# ProDuino.net
KiCad netlist of a schematic drawn in EAGLE
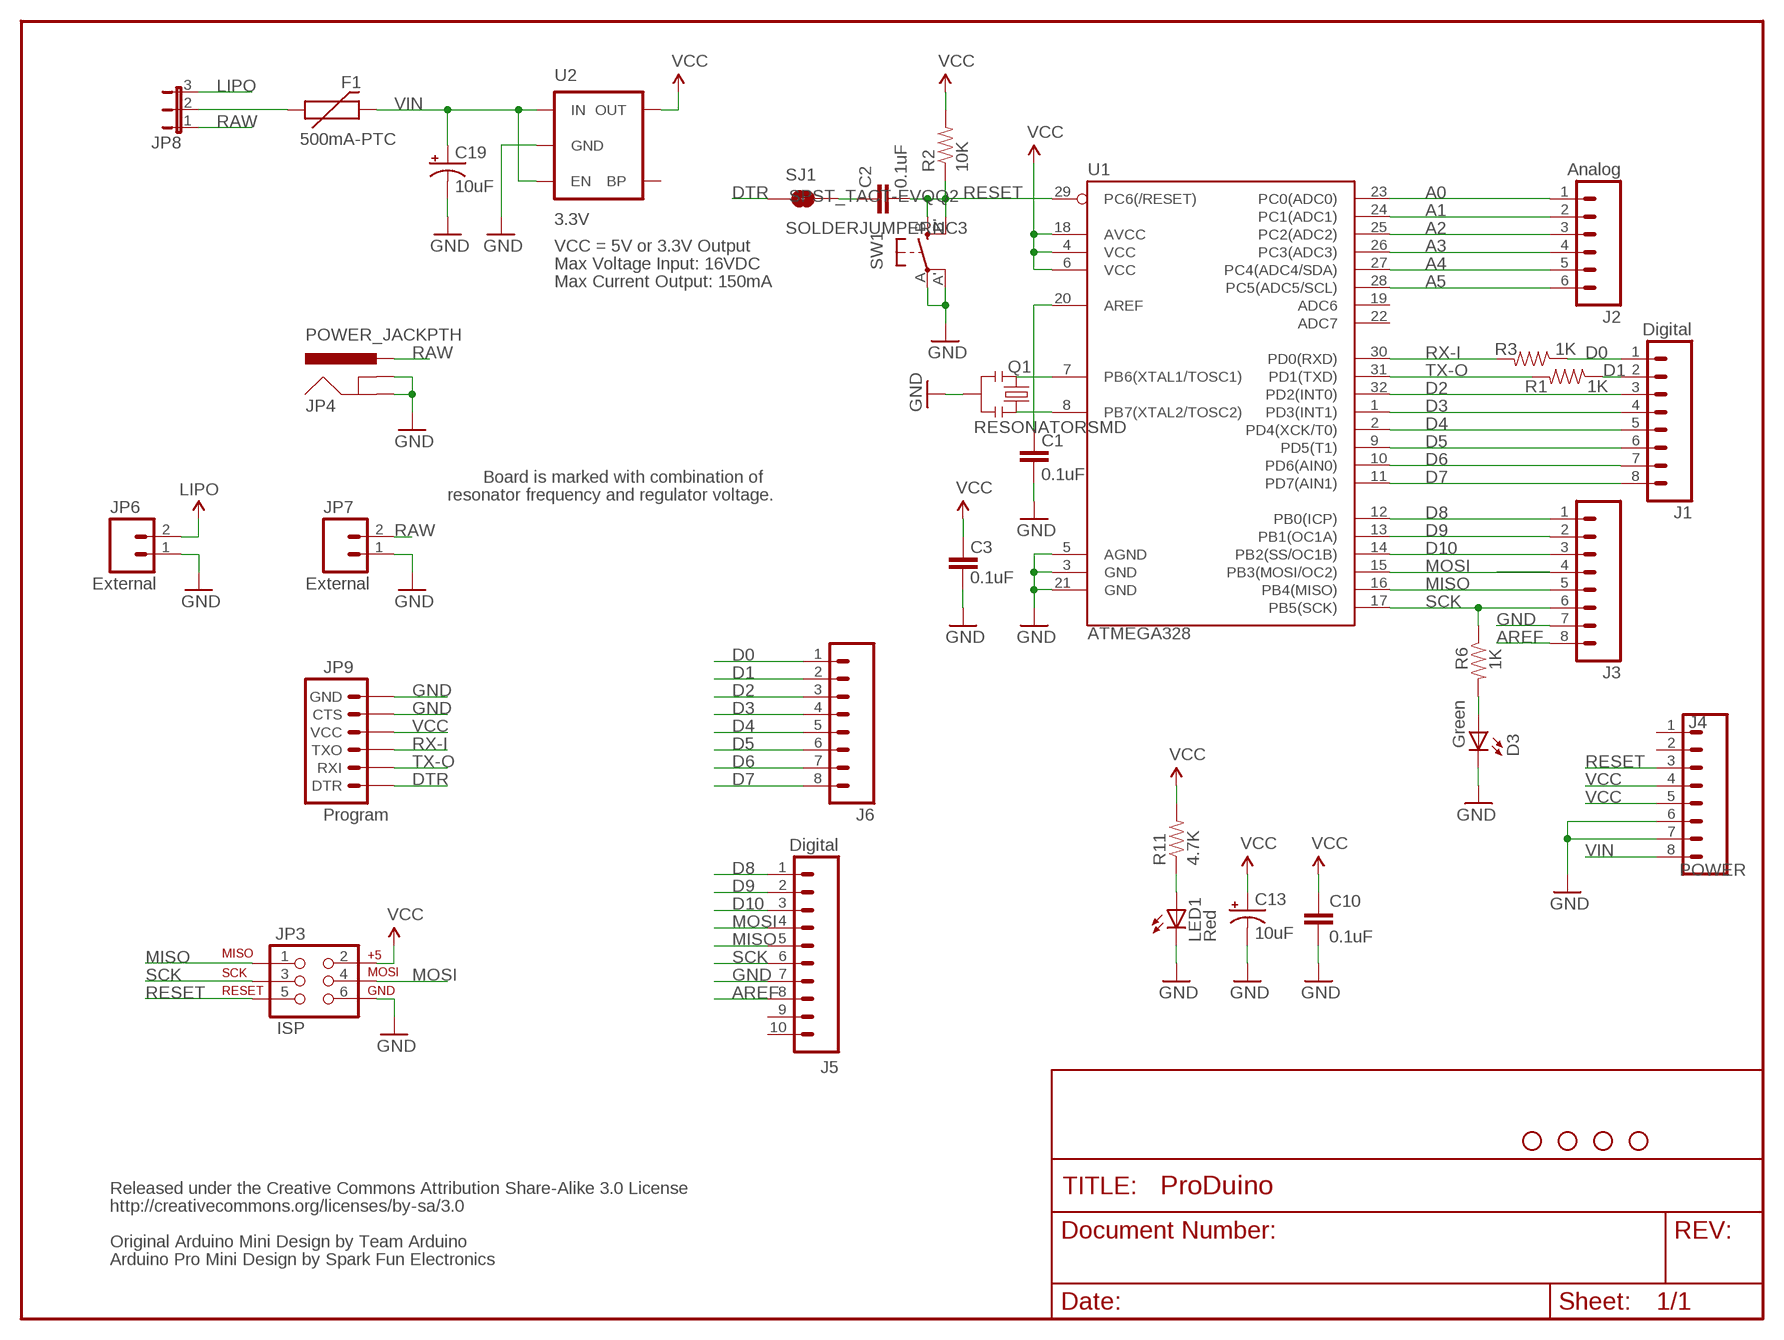
[diagram p0: schematic, sheet 1]

(export (version "E")
  (design (tool "Eeschema 10.0.6"))
  (components
    (comp (ref "C1")
      (value "0.1uF")
      (footprint "eagle-import:0603-CAP")
      (libsource (lib "eagle-import") (part "CAP0603-CAP"))
    )
    (comp (ref "C2")
      (value "0.1uF")
      (footprint "eagle-import:0603-CAP")
      (libsource (lib "eagle-import") (part "CAP0603-CAP"))
    )
    (comp (ref "C3")
      (value "0.1uF")
      (footprint "eagle-import:0603-CAP")
      (libsource (lib "eagle-import") (part "CAP0603-CAP"))
    )
    (comp (ref "C10")
      (value "0.1uF")
      (footprint "eagle-import:0603-CAP")
      (libsource (lib "eagle-import") (part "CAP0603-CAP"))
    )
    (comp (ref "C13")
      (value "10uF")
      (footprint "eagle-import:EIA3216")
      (libsource (lib "eagle-import") (part "CAP_POL1206"))
    )
    (comp (ref "C19")
      (value "10uF")
      (footprint "eagle-import:EIA3216")
      (libsource (lib "eagle-import") (part "CAP_POL1206"))
    )
    (comp (ref "D3")
      (value "Green")
      (footprint "eagle-import:LED-0603")
      (libsource (lib "eagle-import") (part "LED0603"))
    )
    (comp (ref "F1")
      (value "500mA-PTC")
      (footprint "eagle-import:PTC-1206")
      (libsource (lib "eagle-import") (part "PTCSMD"))
    )
    (comp (ref "J1")
      (value "Digital")
      (footprint "eagle-import:1X08")
      (libsource (lib "eagle-import") (part "M081X08"))
    )
    (comp (ref "J2")
      (value "Analog")
      (footprint "eagle-import:1X06")
      (libsource (lib "eagle-import") (part "M06SIP"))
    )
    (comp (ref "J3")
      (value "M081X08")
      (footprint "eagle-import:1X08")
      (libsource (lib "eagle-import") (part "M081X08"))
    )
    (comp (ref "J4")
      (value "POWER")
      (footprint "eagle-import:1X08")
      (libsource (lib "eagle-import") (part "SparkFun-Connectors_M081X08"))
    )
    (comp (ref "J5")
      (value "Digital")
      (footprint "eagle-import:1X10")
      (libsource (lib "eagle-import") (part "M10{dblquote}"))
    )
    (comp (ref "J6")
      (value "M081X08")
      (footprint "eagle-import:1X08")
      (libsource (lib "eagle-import") (part "M081X08"))
    )
    (comp (ref "JP3")
      (value "ISP")
      (footprint "eagle-import:2X3")
      (libsource (lib "eagle-import") (part "AVR_SPI_PRG_6PTH"))
    )
    (comp (ref "JP4")
      (value "POWER_JACKPTH")
      (footprint "eagle-import:POWER_JACK_PTH")
      (libsource (lib "eagle-import") (part "POWER_JACKPTH"))
    )
    (comp (ref "JP6")
      (value "External")
      (footprint "eagle-import:1X02")
      (libsource (lib "eagle-import") (part "M02PTH"))
    )
    (comp (ref "JP7")
      (value "External")
      (footprint "eagle-import:1X02")
      (libsource (lib "eagle-import") (part "M02PTH"))
    )
    (comp (ref "JP8")
      (value "JP2E")
      (footprint "eagle-import:JP2")
      (libsource (lib "eagle-import") (part "JP2E"))
    )
    (comp (ref "JP9")
      (value "Program")
      (footprint "eagle-import:1X06")
      (libsource (lib "eagle-import") (part "ARDUINO_SERIAL_PROGRAMPTH"))
    )
    (comp (ref "LED1")
      (value "Red")
      (footprint "eagle-import:LED-0603")
      (libsource (lib "eagle-import") (part "LED0603"))
    )
    (comp (ref "Q1")
      (value "RESONATORSMD")
      (footprint "eagle-import:RESONATOR-SMD")
      (libsource (lib "eagle-import") (part "RESONATORSMD"))
    )
    (comp (ref "R1")
      (value "1K")
      (footprint "eagle-import:0603-RES")
      (libsource (lib "eagle-import") (part "RESISTOR0603-RES"))
    )
    (comp (ref "R2")
      (value "10K")
      (footprint "eagle-import:0603-RES")
      (libsource (lib "eagle-import") (part "RESISTOR0603-RES"))
    )
    (comp (ref "R3")
      (value "1K")
      (footprint "eagle-import:0603-RES")
      (libsource (lib "eagle-import") (part "RESISTOR0603-RES"))
    )
    (comp (ref "R6")
      (value "1K")
      (footprint "eagle-import:0603-RES")
      (libsource (lib "eagle-import") (part "RESISTOR0603-RES"))
    )
    (comp (ref "R11")
      (value "4.7K")
      (footprint "eagle-import:0603-RES")
      (libsource (lib "eagle-import") (part "RESISTOR0603-RES"))
    )
    (comp (ref "SJ1")
      (value "SOLDERJUMPERNC3")
      (footprint "eagle-import:SJ_2S-NOTRACE")
      (libsource (lib "eagle-import") (part "SOLDERJUMPERNC2"))
    )
    (comp (ref "SW1")
      (value "SPST_TACT-EVQQ2")
      (footprint "eagle-import:EVQ-Q2")
      (libsource (lib "eagle-import") (part "SPST_TACT-EVQQ2"))
    )
    (comp (ref "U$1")
      (value "STAND-OFF")
      (footprint "eagle-import:STAND-OFF")
      (libsource (lib "eagle-import") (part "STAND-OFF"))
    )
    (comp (ref "U$3")
      (value "STAND-OFF")
      (footprint "eagle-import:STAND-OFF")
      (libsource (lib "eagle-import") (part "STAND-OFF"))
    )
    (comp (ref "U$9")
      (value "STAND-OFF")
      (footprint "eagle-import:STAND-OFF")
      (libsource (lib "eagle-import") (part "STAND-OFF"))
    )
    (comp (ref "U$10")
      (value "STAND-OFF")
      (footprint "eagle-import:STAND-OFF")
      (libsource (lib "eagle-import") (part "STAND-OFF"))
    )
    (comp (ref "U1")
      (value "ATMEGA328")
      (footprint "eagle-import:TQFP32-08")
      (libsource (lib "eagle-import") (part "ATMEGA168"))
    )
    (comp (ref "U2")
      (value "3.3V")
      (footprint "eagle-import:SOT23-5")
      (libsource (lib "eagle-import") (part "V_REG_LDOSMD"))
    )
  )
  (nets
    (net (code "1") (name "/A0") (class "Default")
      (node (ref "J2") (pin "1") (pinfunction "1_1") (pintype "passive"))
      (node (ref "U1") (pin "23") (pinfunction "PC0(ADC0)_23") (pintype "bidirectional"))
    )
    (net (code "2") (name "/A1") (class "Default")
      (node (ref "J2") (pin "2") (pinfunction "2_2") (pintype "passive"))
      (node (ref "U1") (pin "24") (pinfunction "PC1(ADC1)_24") (pintype "bidirectional"))
    )
    (net (code "3") (name "/A2") (class "Default")
      (node (ref "J2") (pin "3") (pinfunction "3_3") (pintype "passive"))
      (node (ref "U1") (pin "25") (pinfunction "PC2(ADC2)_25") (pintype "bidirectional"))
    )
    (net (code "4") (name "/A3") (class "Default")
      (node (ref "J2") (pin "4") (pinfunction "4_4") (pintype "passive"))
      (node (ref "U1") (pin "26") (pinfunction "PC3(ADC3)_26") (pintype "bidirectional"))
    )
    (net (code "5") (name "/A4") (class "Default")
      (node (ref "J2") (pin "5") (pinfunction "5_5") (pintype "passive"))
      (node (ref "U1") (pin "27") (pinfunction "PC4(ADC4/SDA)_27") (pintype "bidirectional"))
    )
    (net (code "6") (name "/A5") (class "Default")
      (node (ref "J2") (pin "6") (pinfunction "6_6") (pintype "passive"))
      (node (ref "U1") (pin "28") (pinfunction "PC5(ADC5/SCL)_28") (pintype "bidirectional"))
    )
    (net (code "7") (name "/AREF") (class "Default")
      (node (ref "C1") (pin "2") (pinfunction "2_2") (pintype "passive"))
      (node (ref "J3") (pin "8") (pinfunction "8_8") (pintype "passive"))
      (node (ref "J5") (pin "8") (pinfunction "8_8") (pintype "passive"))
      (node (ref "U1") (pin "20") (pinfunction "AREF_20") (pintype "bidirectional"))
    )
    (net (code "8") (name "/D0") (class "Default")
      (node (ref "J1") (pin "1") (pinfunction "1_1") (pintype "passive"))
      (node (ref "J6") (pin "1") (pinfunction "1_1") (pintype "passive"))
      (node (ref "R3") (pin "1") (pinfunction "1_1") (pintype "passive"))
    )
    (net (code "9") (name "/D1") (class "Default")
      (node (ref "J1") (pin "2") (pinfunction "2_2") (pintype "passive"))
      (node (ref "J6") (pin "2") (pinfunction "2_2") (pintype "passive"))
      (node (ref "R1") (pin "1") (pinfunction "1_1") (pintype "passive"))
    )
    (net (code "10") (name "/D2") (class "Default")
      (node (ref "J1") (pin "3") (pinfunction "3_3") (pintype "passive"))
      (node (ref "J6") (pin "3") (pinfunction "3_3") (pintype "passive"))
      (node (ref "U1") (pin "32") (pinfunction "PD2(INT0)_32") (pintype "bidirectional"))
    )
    (net (code "11") (name "/D3") (class "Default")
      (node (ref "J1") (pin "4") (pinfunction "4_4") (pintype "passive"))
      (node (ref "J6") (pin "4") (pinfunction "4_4") (pintype "passive"))
      (node (ref "U1") (pin "1") (pinfunction "PD3(INT1)_1") (pintype "bidirectional"))
    )
    (net (code "12") (name "/D4") (class "Default")
      (node (ref "J1") (pin "5") (pinfunction "5_5") (pintype "passive"))
      (node (ref "J6") (pin "5") (pinfunction "5_5") (pintype "passive"))
      (node (ref "U1") (pin "2") (pinfunction "PD4(XCK/T0)_2") (pintype "bidirectional"))
    )
    (net (code "13") (name "/D5") (class "Default")
      (node (ref "J1") (pin "6") (pinfunction "6_6") (pintype "passive"))
      (node (ref "J6") (pin "6") (pinfunction "6_6") (pintype "passive"))
      (node (ref "U1") (pin "9") (pinfunction "PD5(T1)_9") (pintype "bidirectional"))
    )
    (net (code "14") (name "/D6") (class "Default")
      (node (ref "J1") (pin "7") (pinfunction "7_7") (pintype "passive"))
      (node (ref "J6") (pin "7") (pinfunction "7_7") (pintype "passive"))
      (node (ref "U1") (pin "10") (pinfunction "PD6(AIN0)_10") (pintype "bidirectional"))
    )
    (net (code "15") (name "/D7") (class "Default")
      (node (ref "J1") (pin "8") (pinfunction "8_8") (pintype "passive"))
      (node (ref "J6") (pin "8") (pinfunction "8_8") (pintype "passive"))
      (node (ref "U1") (pin "11") (pinfunction "PD7(AIN1)_11") (pintype "bidirectional"))
    )
    (net (code "16") (name "/D8") (class "Default")
      (node (ref "J3") (pin "1") (pinfunction "1_1") (pintype "passive"))
      (node (ref "J5") (pin "1") (pinfunction "1_1") (pintype "passive"))
      (node (ref "U1") (pin "12") (pinfunction "PB0(ICP)_12") (pintype "bidirectional"))
    )
    (net (code "17") (name "/D9") (class "Default")
      (node (ref "J3") (pin "2") (pinfunction "2_2") (pintype "passive"))
      (node (ref "J5") (pin "2") (pinfunction "2_2") (pintype "passive"))
      (node (ref "U1") (pin "13") (pinfunction "PB1(OC1A)_13") (pintype "bidirectional"))
    )
    (net (code "18") (name "/D10") (class "Default")
      (node (ref "J3") (pin "3") (pinfunction "3_3") (pintype "passive"))
      (node (ref "J5") (pin "3") (pinfunction "3_3") (pintype "passive"))
      (node (ref "U1") (pin "14") (pinfunction "PB2(SS/OC1B)_14") (pintype "bidirectional"))
    )
    (net (code "19") (name "/DTR") (class "Default")
      (node (ref "JP9") (pin "1") (pinfunction "DTR_1") (pintype "passive"))
      (node (ref "SJ1") (pin "1") (pinfunction "1_1") (pintype "passive"))
    )
    (net (code "20") (name "/MISO") (class "Default")
      (node (ref "J3") (pin "5") (pinfunction "5_5") (pintype "passive"))
      (node (ref "J5") (pin "5") (pinfunction "5_5") (pintype "passive"))
      (node (ref "JP3") (pin "1") (pinfunction "1_1") (pintype "passive"))
      (node (ref "U1") (pin "16") (pinfunction "PB4(MISO)_16") (pintype "bidirectional"))
    )
    (net (code "21") (name "/MOSI") (class "Default")
      (node (ref "J3") (pin "4") (pinfunction "4_4") (pintype "passive"))
      (node (ref "J5") (pin "4") (pinfunction "4_4") (pintype "passive"))
      (node (ref "JP3") (pin "4") (pinfunction "4_4") (pintype "passive"))
      (node (ref "U1") (pin "15") (pinfunction "PB3(MOSI/OC2)_15") (pintype "bidirectional"))
    )
    (net (code "22") (name "/RAW") (class "Default")
      (node (ref "JP4") (pin "PWR") (pinfunction "PWR_PWR") (pintype "bidirectional"))
      (node (ref "JP7") (pin "2") (pinfunction "2_2") (pintype "passive"))
      (node (ref "JP8") (pin "1") (pinfunction "1_1") (pintype "passive"))
    )
    (net (code "23") (name "/RESET") (class "Default")
      (node (ref "C2") (pin "2") (pinfunction "2_2") (pintype "passive"))
      (node (ref "J4") (pin "3") (pinfunction "3_3") (pintype "passive"))
      (node (ref "JP3") (pin "5") (pinfunction "5_5") (pintype "passive"))
      (node (ref "R2") (pin "1") (pinfunction "1_1") (pintype "passive"))
      (node (ref "SW1") (pin "B") (pinfunction "S_B") (pintype "passive"))
      (node (ref "SW1") (pin "B'") (pinfunction "S1_B'") (pintype "passive"))
      (node (ref "U1") (pin "29") (pinfunction "PC6(/RESET)_29") (pintype "bidirectional"))
    )
    (net (code "24") (name "/RX-I") (class "Default")
      (node (ref "JP9") (pin "3") (pinfunction "TXO_3") (pintype "passive"))
      (node (ref "R3") (pin "2") (pinfunction "2_2") (pintype "passive"))
      (node (ref "U1") (pin "30") (pinfunction "PD0(RXD)_30") (pintype "bidirectional"))
    )
    (net (code "25") (name "/SCK") (class "Default")
      (node (ref "J3") (pin "6") (pinfunction "6_6") (pintype "passive"))
      (node (ref "J5") (pin "6") (pinfunction "6_6") (pintype "passive"))
      (node (ref "JP3") (pin "3") (pinfunction "3_3") (pintype "passive"))
      (node (ref "R6") (pin "1") (pinfunction "1_1") (pintype "passive"))
      (node (ref "U1") (pin "17") (pinfunction "PB5(SCK)_17") (pintype "bidirectional"))
    )
    (net (code "26") (name "/TX-O") (class "Default")
      (node (ref "JP9") (pin "2") (pinfunction "RXI_2") (pintype "passive"))
      (node (ref "R1") (pin "2") (pinfunction "2_2") (pintype "passive"))
      (node (ref "U1") (pin "31") (pinfunction "PD1(TXD)_31") (pintype "bidirectional"))
    )
    (net (code "27") (name "/VIN") (class "Default")
      (node (ref "C19") (pin "A") (pinfunction "+_A") (pintype "passive"))
      (node (ref "F1") (pin "2") (pinfunction "2_2") (pintype "bidirectional"))
      (node (ref "J4") (pin "8") (pinfunction "8_8") (pintype "passive"))
      (node (ref "U2") (pin "1") (pinfunction "IN_1") (pintype "input"))
      (node (ref "U2") (pin "3") (pinfunction "EN_3") (pintype "input"))
    )
    (net (code "28") (name "GND") (class "Default")
      (node (ref "C1") (pin "1") (pinfunction "1_1") (pintype "passive"))
      (node (ref "C10") (pin "2") (pinfunction "2_2") (pintype "passive"))
      (node (ref "C13") (pin "C") (pinfunction "-_C") (pintype "passive"))
      (node (ref "C19") (pin "C") (pinfunction "-_C") (pintype "passive"))
      (node (ref "C3") (pin "1") (pinfunction "1_1") (pintype "passive"))
      (node (ref "D3") (pin "C") (pinfunction "C_C") (pintype "passive"))
      (node (ref "J3") (pin "7") (pinfunction "7_7") (pintype "passive"))
      (node (ref "J4") (pin "6") (pinfunction "6_6") (pintype "passive"))
      (node (ref "J4") (pin "7") (pinfunction "7_7") (pintype "passive"))
      (node (ref "J5") (pin "7") (pinfunction "7_7") (pintype "passive"))
      (node (ref "JP3") (pin "6") (pinfunction "6_6") (pintype "passive"))
      (node (ref "JP4") (pin "GND") (pinfunction "GND_GND") (pintype "bidirectional"))
      (node (ref "JP4") (pin "GNDBREAK") (pinfunction "GNDBREAK_GNDBREAK") (pintype "bidirectional"))
      (node (ref "JP6") (pin "1") (pinfunction "1_1") (pintype "passive"))
      (node (ref "JP7") (pin "1") (pinfunction "1_1") (pintype "passive"))
      (node (ref "JP9") (pin "5") (pinfunction "CTS_5") (pintype "passive"))
      (node (ref "JP9") (pin "6") (pinfunction "GND_6") (pintype "passive"))
      (node (ref "LED1") (pin "C") (pinfunction "C_C") (pintype "passive"))
      (node (ref "Q1") (pin "2") (pinfunction "2_2") (pintype "passive"))
      (node (ref "SW1") (pin "A") (pinfunction "P_A") (pintype "passive"))
      (node (ref "SW1") (pin "A'") (pinfunction "P1_A'") (pintype "passive"))
      (node (ref "U1") (pin "21") (pinfunction "GND_21") (pintype "bidirectional"))
      (node (ref "U1") (pin "3") (pinfunction "GND_3") (pintype "bidirectional"))
      (node (ref "U1") (pin "5") (pinfunction "AGND_5") (pintype "bidirectional"))
      (node (ref "U2") (pin "2") (pinfunction "GND_2") (pintype "input"))
    )
    (net (code "29") (name "LIPO") (class "Default")
      (node (ref "JP6") (pin "2") (pinfunction "2_2") (pintype "passive"))
      (node (ref "JP8") (pin "3") (pinfunction "3_3") (pintype "passive"))
    )
    (net (code "30") (name "Net-(C2-Pad1)") (class "Default")
      (node (ref "C2") (pin "1") (pinfunction "1_1") (pintype "passive"))
      (node (ref "SJ1") (pin "2") (pinfunction "2_2") (pintype "passive"))
    )
    (net (code "31") (name "Net-(D3-PadA)") (class "Default")
      (node (ref "D3") (pin "A") (pinfunction "A_A") (pintype "passive"))
      (node (ref "R6") (pin "2") (pinfunction "2_2") (pintype "passive"))
    )
    (net (code "32") (name "Net-(F1-Pad1)") (class "Default")
      (node (ref "F1") (pin "1") (pinfunction "1_1") (pintype "bidirectional"))
      (node (ref "JP8") (pin "2") (pinfunction "2_2") (pintype "passive"))
    )
    (net (code "33") (name "Net-(LED1-PadA)") (class "Default")
      (node (ref "LED1") (pin "A") (pinfunction "A_A") (pintype "passive"))
      (node (ref "R11") (pin "1") (pinfunction "1_1") (pintype "passive"))
    )
    (net (code "34") (name "Net-(U1-PB6(XTAL1{slash}TOSC1))") (class "Default")
      (node (ref "Q1") (pin "3") (pinfunction "3_3") (pintype "passive"))
      (node (ref "U1") (pin "7") (pinfunction "PB6(XTAL1/TOSC1)_7") (pintype "bidirectional"))
    )
    (net (code "35") (name "Net-(U1-PB7(XTAL2{slash}TOSC2))") (class "Default")
      (node (ref "Q1") (pin "1") (pinfunction "1_1") (pintype "passive"))
      (node (ref "U1") (pin "8") (pinfunction "PB7(XTAL2/TOSC2)_8") (pintype "bidirectional"))
    )
    (net (code "36") (name "VCC") (class "Default")
      (node (ref "C10") (pin "1") (pinfunction "1_1") (pintype "passive"))
      (node (ref "C13") (pin "A") (pinfunction "+_A") (pintype "passive"))
      (node (ref "C3") (pin "2") (pinfunction "2_2") (pintype "passive"))
      (node (ref "J4") (pin "4") (pinfunction "4_4") (pintype "passive"))
      (node (ref "J4") (pin "5") (pinfunction "5_5") (pintype "passive"))
      (node (ref "JP3") (pin "2") (pinfunction "2_2") (pintype "passive"))
      (node (ref "JP9") (pin "4") (pinfunction "VCC_4") (pintype "passive"))
      (node (ref "R11") (pin "2") (pinfunction "2_2") (pintype "passive"))
      (node (ref "R2") (pin "2") (pinfunction "2_2") (pintype "passive"))
      (node (ref "U1") (pin "18") (pinfunction "AVCC_18") (pintype "bidirectional"))
      (node (ref "U1") (pin "4") (pinfunction "VCC_4") (pintype "bidirectional"))
      (node (ref "U1") (pin "6") (pinfunction "VCC_6") (pintype "bidirectional"))
      (node (ref "U2") (pin "5") (pinfunction "OUT_5") (pintype "passive"))
    )
    (net (code "37") (name "unconnected-(J4-Pad1)") (class "Default")
      (node (ref "J4") (pin "1") (pinfunction "1_1") (pintype "passive"))
    )
    (net (code "38") (name "unconnected-(J4-Pad2)") (class "Default")
      (node (ref "J4") (pin "2") (pinfunction "2_2") (pintype "passive"))
    )
    (net (code "39") (name "unconnected-(J5-Pad9)") (class "Default")
      (node (ref "J5") (pin "9") (pinfunction "9_9") (pintype "passive"))
    )
    (net (code "40") (name "unconnected-(J5-Pad10)") (class "Default")
      (node (ref "J5") (pin "10") (pinfunction "10_10") (pintype "passive"))
    )
    (net (code "41") (name "unconnected-(U1-ADC6-Pad19)") (class "Default")
      (node (ref "U1") (pin "19") (pinfunction "ADC6_19") (pintype "bidirectional"))
    )
    (net (code "42") (name "unconnected-(U1-ADC7-Pad22)") (class "Default")
      (node (ref "U1") (pin "22") (pinfunction "ADC7_22") (pintype "bidirectional"))
    )
    (net (code "43") (name "unconnected-(U2-BP-Pad4)") (class "Default")
      (node (ref "U2") (pin "4") (pinfunction "BP_4") (pintype "input"))
    )
  )
)
